# FlybackDriverZVS.net
KiCad netlist of a schematic drawn in Altium Designer
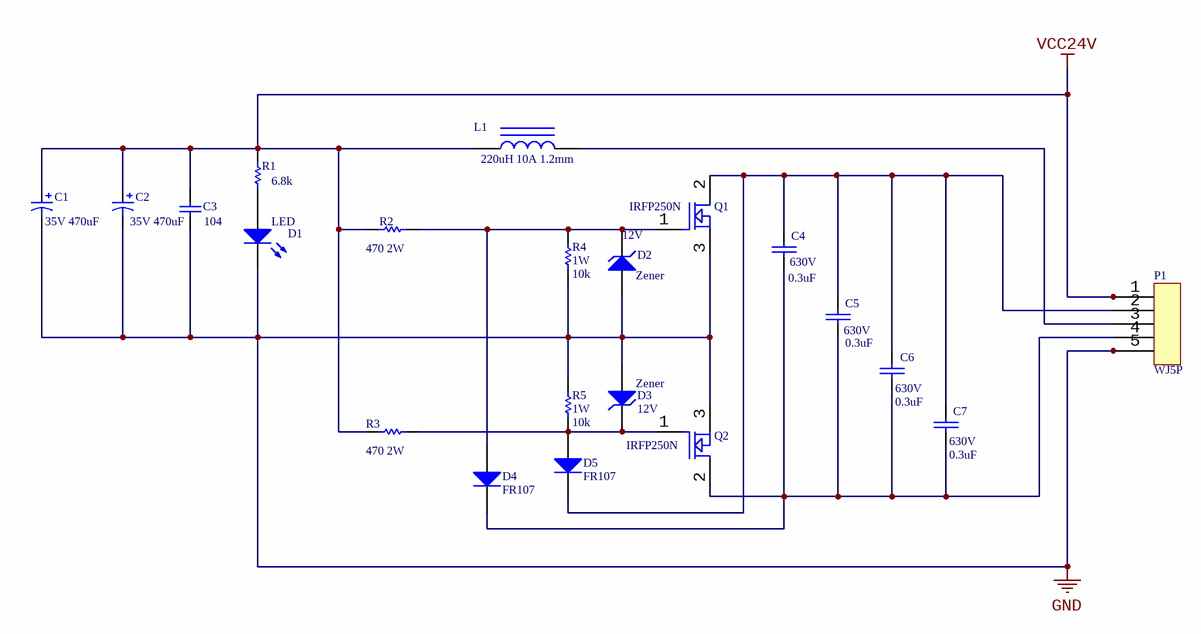
[diagram p0: FlybackDriverZVS.SchDoc]

(export (version "E")
  (design (tool "Eeschema 10.0.6"))
  (components
    (comp (ref "C1")
      (value "35V 470uF")
      (footprint "C4_5_10mm")
      (description "Polarized Capacitor (Radial)")
      (fields (field (name "PUBLISHER") "Altium Limited"))
      (libsource (lib "Miscellaneous Devices") (part "Cap Pol1"))
    )
    (comp (ref "C2")
      (value "35V 470uF")
      (footprint "C4_5_10mm")
      (description "Polarized Capacitor (Radial)")
      (fields (field (name "PUBLISHER") "Altium Limited"))
      (libsource (lib "Miscellaneous Devices") (part "Cap Pol1"))
    )
    (comp (ref "C3")
      (value "104")
      (footprint "RAD-0.3")
      (description "Capacitor")
      (fields (field (name "PUBLISHER") "Altium Limited"))
      (libsource (lib "Miscellaneous Devices") (part "Cap"))
    )
    (comp (ref "C4")
      (value "630V")
      (footprint "MKP_Capacitor")
      (description "Capacitor")
      (fields (field (name "CAPACITANCE") "0.3uF"))
      (libsource (lib "电容") (part "普通电容"))
    )
    (comp (ref "C5")
      (value "630V")
      (footprint "MKP_Capacitor")
      (description "Capacitor")
      (fields (field (name "CAPACITANCE") "0.3uF"))
      (libsource (lib "电容") (part "普通电容"))
    )
    (comp (ref "C6")
      (value "630V")
      (footprint "MKP_Capacitor")
      (description "Capacitor")
      (fields (field (name "CAPACITANCE") "0.3uF"))
      (libsource (lib "电容") (part "普通电容"))
    )
    (comp (ref "C7")
      (value "630V")
      (footprint "MKP_Capacitor")
      (description "Capacitor")
      (fields (field (name "CAPACITANCE") "0.3uF"))
      (libsource (lib "电容") (part "普通电容"))
    )
    (comp (ref "D1")
      (value "~")
      (footprint "0805")
      (description "Typical BLUE SiC LED")
      (fields (field (name "PUBLISHER") "Altium Limited"))
      (libsource (lib "Miscellaneous Devices") (part "LED3"))
    )
    (comp (ref "D2")
      (value "12V")
      (footprint "DIODE-0.4")
      (description "Zener Diode")
      (fields (field (name "PUBLISHER") "Altium Limited"))
      (libsource (lib "Miscellaneous Devices") (part "D Zener"))
    )
    (comp (ref "D3")
      (value "12V")
      (footprint "DIODE-0.4")
      (description "Zener Diode")
      (fields (field (name "PUBLISHER") "Altium Limited"))
      (libsource (lib "Miscellaneous Devices") (part "D Zener"))
    )
    (comp (ref "D4")
      (value "FR107")
      (footprint "DIODE-0.4")
      (description "1 Amp General Purpose Rectifier")
      (fields (field (name "PUBLISHER") "Altium Limited"))
      (libsource (lib "Miscellaneous Devices") (part "Diode 1N4007"))
    )
    (comp (ref "D5")
      (value "FR107")
      (footprint "DIODE-0.4")
      (description "1 Amp General Purpose Rectifier")
      (fields (field (name "PUBLISHER") "Altium Limited"))
      (libsource (lib "Miscellaneous Devices") (part "Diode 1N4007"))
    )
    (comp (ref "L1")
      (value "220uH 10A 1.2mm")
      (footprint "HBL_30_10_H")
      (description "Magnetic-Core Inductor")
      (fields (field (name "PUBLISHER") "Altium Limited"))
      (libsource (lib "Miscellaneous Devices") (part "Inductor Iron"))
    )
    (comp (ref "P1") (value "WJ5P") (footprint "CJ_10x5") (libsource (lib "WJ381") (part "WJ5P_381")))
    (comp (ref "Q1")
      (value "IRFP250N")
      (footprint "TO-247AC_ZCEDGE")
      (libsource (lib "场效应管及可控硅") (part "MOSFET N"))
    )
    (comp (ref "Q2")
      (value "IRFP250N")
      (footprint "TO-247AC_ZCEDGE")
      (libsource (lib "场效应管及可控硅") (part "MOSFET N"))
    )
    (comp (ref "R1")
      (value "6.8k")
      (footprint "AXIAL-0.3")
      (description "Resistor")
      (fields (field (name "PUBLISHER") "Altium Limited"))
      (libsource (lib "Miscellaneous Devices") (part "Res1"))
    )
    (comp (ref "R2")
      (value "470 2W")
      (footprint "2WZC")
      (description "Resistor")
      (fields (field (name "PUBLISHER") "Altium Limited"))
      (libsource (lib "Miscellaneous Devices") (part "Res1"))
    )
    (comp (ref "R3")
      (value "470 2W")
      (footprint "2WZC")
      (description "Resistor")
      (fields (field (name "PUBLISHER") "Altium Limited"))
      (libsource (lib "Miscellaneous Devices") (part "Res1"))
    )
    (comp (ref "R4")
      (value "1W")
      (footprint "1WZC")
      (description "Resistor")
      (fields (field (name "ALTIUM_VALUE") "10k") (field (name "PUBLISHER") "Altium Limited"))
      (libsource (lib "Miscellaneous Devices") (part "Res1"))
    )
    (comp (ref "R5")
      (value "1W")
      (footprint "1WZC")
      (description "Resistor")
      (fields (field (name "ALTIUM_VALUE") "10k") (field (name "PUBLISHER") "Altium Limited"))
      (libsource (lib "Miscellaneous Devices") (part "Res1"))
    )
  )
  (nets
    (net (code "1") (name "GND") (class "Default")
      (node (ref "C1") (pin "2") (pinfunction "2_2") (pintype "passive"))
      (node (ref "C2") (pin "2") (pinfunction "2_2") (pintype "passive"))
      (node (ref "C3") (pin "1") (pinfunction "1_1") (pintype "passive"))
      (node (ref "D1") (pin "2") (pinfunction "K_2") (pintype "passive"))
      (node (ref "D2") (pin "1") (pinfunction "A_1") (pintype "passive"))
      (node (ref "D3") (pin "1") (pinfunction "A_1") (pintype "passive"))
      (node (ref "P1") (pin "5") (pintype "passive"))
      (node (ref "Q1") (pin "3") (pinfunction "S_3") (pintype "passive"))
      (node (ref "Q2") (pin "3") (pinfunction "S_3") (pintype "passive"))
      (node (ref "R4") (pin "2") (pinfunction "2_2") (pintype "passive"))
      (node (ref "R5") (pin "1") (pinfunction "1_1") (pintype "passive"))
    )
    (net (code "2") (name "Net-(D1-A)") (class "Default")
      (node (ref "D1") (pin "1") (pinfunction "A_1") (pintype "passive"))
      (node (ref "R1") (pin "1") (pinfunction "1_1") (pintype "passive"))
    )
    (net (code "3") (name "Net-(D2-K)") (class "Default")
      (node (ref "D2") (pin "2") (pinfunction "K_2") (pintype "passive"))
      (node (ref "D4") (pin "1") (pinfunction "A_1") (pintype "passive"))
      (node (ref "Q1") (pin "1") (pinfunction "G_1") (pintype "passive"))
      (node (ref "R2") (pin "1") (pinfunction "1_1") (pintype "passive"))
      (node (ref "R4") (pin "1") (pinfunction "1_1") (pintype "passive"))
    )
    (net (code "4") (name "Net-(D3-K)") (class "Default")
      (node (ref "D3") (pin "2") (pinfunction "K_2") (pintype "passive"))
      (node (ref "D5") (pin "1") (pinfunction "A_1") (pintype "passive"))
      (node (ref "Q2") (pin "1") (pinfunction "G_1") (pintype "passive"))
      (node (ref "R3") (pin "1") (pinfunction "1_1") (pintype "passive"))
      (node (ref "R5") (pin "2") (pinfunction "2_2") (pintype "passive"))
    )
    (net (code "5") (name "Net-(D4-K)") (class "Default")
      (node (ref "C4") (pin "2") (pinfunction "2_2") (pintype "passive"))
      (node (ref "C5") (pin "2") (pinfunction "2_2") (pintype "passive"))
      (node (ref "C6") (pin "2") (pinfunction "2_2") (pintype "passive"))
      (node (ref "C7") (pin "2") (pinfunction "2_2") (pintype "passive"))
      (node (ref "D4") (pin "2") (pinfunction "K_2") (pintype "passive"))
      (node (ref "P1") (pin "4") (pintype "passive"))
      (node (ref "Q2") (pin "2") (pinfunction "D_2") (pintype "passive"))
    )
    (net (code "6") (name "Net-(D5-K)") (class "Default")
      (node (ref "C4") (pin "1") (pinfunction "1_1") (pintype "passive"))
      (node (ref "C5") (pin "1") (pinfunction "1_1") (pintype "passive"))
      (node (ref "C6") (pin "1") (pinfunction "1_1") (pintype "passive"))
      (node (ref "C7") (pin "1") (pinfunction "1_1") (pintype "passive"))
      (node (ref "D5") (pin "2") (pinfunction "K_2") (pintype "passive"))
      (node (ref "P1") (pin "2") (pintype "passive"))
      (node (ref "Q1") (pin "2") (pinfunction "D_2") (pintype "passive"))
    )
    (net (code "7") (name "Net-(L1-Pad2)") (class "Default")
      (node (ref "L1") (pin "2") (pinfunction "2_2") (pintype "passive"))
      (node (ref "P1") (pin "3") (pintype "passive"))
    )
    (net (code "8") (name "VCC24V") (class "Default")
      (node (ref "C1") (pin "1") (pinfunction "1_1") (pintype "passive"))
      (node (ref "C2") (pin "1") (pinfunction "1_1") (pintype "passive"))
      (node (ref "C3") (pin "2") (pinfunction "2_2") (pintype "passive"))
      (node (ref "L1") (pin "1") (pinfunction "1_1") (pintype "passive"))
      (node (ref "P1") (pin "1") (pintype "passive"))
      (node (ref "R1") (pin "2") (pinfunction "2_2") (pintype "passive"))
      (node (ref "R2") (pin "2") (pinfunction "2_2") (pintype "passive"))
      (node (ref "R3") (pin "2") (pinfunction "2_2") (pintype "passive"))
    )
  )
)
